# esp32.net
KiCad netlist of a schematic drawn in Altium Designer
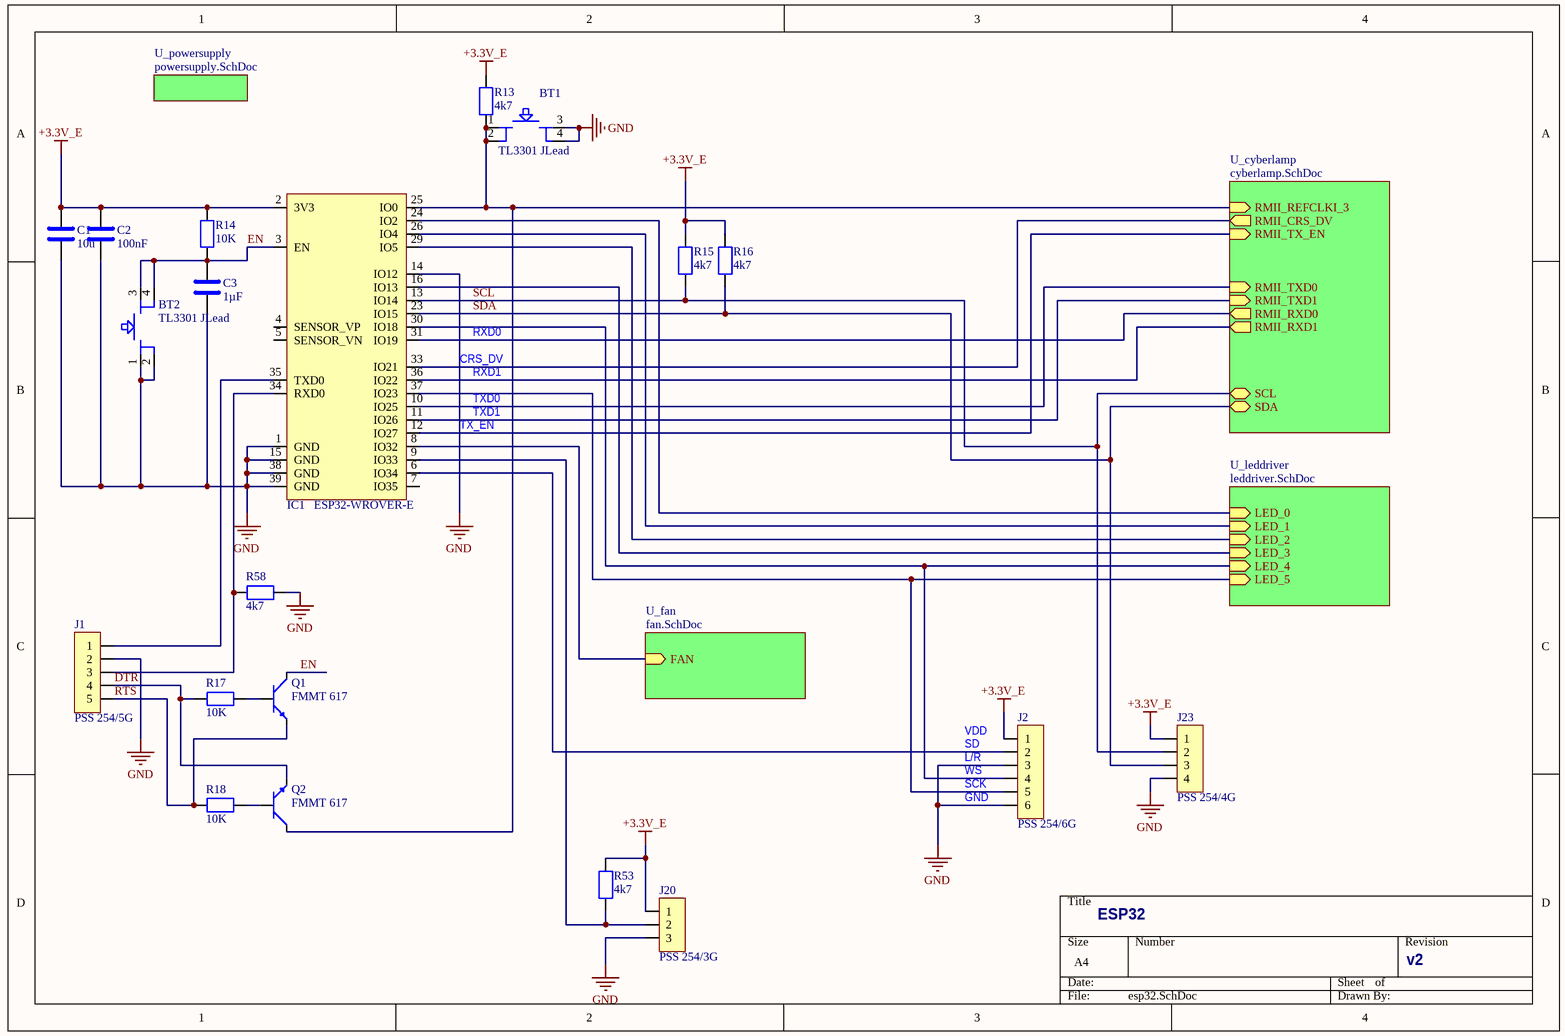
[diagram p0: esp32.SchDoc]

(export (version "E")
  (design (tool "Eeschema 10.0.6"))
  (components
    (comp (ref "BT1")
      (value "TL3301 JLead")
      (footprint "TL3301_Jlead")
      (description "TL3301 J-Lead button")
      (libsource (lib "switch_relais") (part "TK3301_jlead"))
    )
    (comp (ref "BT2")
      (value "TL3301 JLead")
      (footprint "TL3301_Jlead")
      (description "TL3301 J-Lead button")
      (libsource (lib "switch_relais") (part "TK3301_jlead"))
    )
    (comp (ref "C1")
      (value "10u")
      (footprint "1210")
      (description "10uF 63V X7R 1210")
      (fields (field (name "MOUSER PART") "81-GRM32ER71J106MA2L") (field (name "VOLTAGE") "63V"))
      (libsource (lib "capacitors") (part "10uF 63V X7R 1210"))
    )
    (comp (ref "C2")
      (value "100nF")
      (footprint "0603")
      (description "100nF 50V MLCC 0603")
      (fields (field (name "VOLTAGE") "50V"))
      (libsource (lib "capacitors") (part "100nF 50V MLCC 0603"))
    )
    (comp (ref "C3")
      (value "1µF")
      (footprint "0805")
      (description "1µF 25V MLCC 0805")
      (fields (field (name "VOLTAGE") "25V"))
      (libsource (lib "capacitor0805") (part "1µF 25V MLCC 0805"))
    )
    (comp (ref "IC1")
      (value "ESP32-WROVER-E")
      (footprint "ESP32-WROVER-I")
      (libsource (lib "microcontroller") (part "ESP32-WROVER-E-N16R2"))
    )
    (comp (ref "J1")
      (value "PSS 254/5G")
      (footprint "PSS 5pol")
      (description "PSS 5pol wire-to-board-connector")
      (libsource (lib "connectors_pss") (part "PSS 254/5G"))
    )
    (comp (ref "J2")
      (value "PSS 254/6G")
      (footprint "PSS 6pol")
      (description "PSS 6pol wire-to-board-connector")
      (libsource (lib "connectors_pss") (part "PSS 254/6G"))
    )
    (comp (ref "J20")
      (value "PSS 254/3G")
      (footprint "PSS 3pol")
      (description "PSS 3pol wire-to-board-connector")
      (libsource (lib "connectors_pss") (part "PSS 254/3G"))
    )
    (comp (ref "J23")
      (value "PSS 254/4G")
      (footprint "PSS 4pol")
      (description "PSS 4pol wire-to-board-connector")
      (libsource (lib "connectors_pss") (part "PSS 254/4G"))
    )
    (comp (ref "Q1")
      (value "FMMT 617")
      (footprint "SOT-23")
      (description "NPN switching Transistor, 3A")
      (libsource (lib "semiconductors") (part "FMMT 617"))
    )
    (comp (ref "Q2")
      (value "FMMT 617")
      (footprint "SOT-23")
      (description "NPN switching Transistor, 3A")
      (libsource (lib "semiconductors") (part "FMMT 617"))
    )
    (comp (ref "R13")
      (value "4k7")
      (footprint "res0603")
      (description "4k7 100mW 0603")
      (libsource (lib "resistors") (part "4k7 100mW 0603"))
    )
    (comp (ref "R14")
      (value "10K")
      (footprint "res0603")
      (description "10K 100mW 0603")
      (fields (field (name "TOLERANCE") "1%"))
      (libsource (lib "resistors") (part "10K 100mW 0603"))
    )
    (comp (ref "R15")
      (value "4k7")
      (footprint "res0603")
      (description "4k7 100mW 0603")
      (libsource (lib "resistors") (part "4k7 100mW 0603"))
    )
    (comp (ref "R16")
      (value "4k7")
      (footprint "res0603")
      (description "4k7 100mW 0603")
      (libsource (lib "resistors") (part "4k7 100mW 0603"))
    )
    (comp (ref "R17")
      (value "10K")
      (footprint "res0603")
      (description "10K 100mW 0603")
      (fields (field (name "TOLERANCE") "1%"))
      (libsource (lib "resistors") (part "10K 100mW 0603"))
    )
    (comp (ref "R18")
      (value "10K")
      (footprint "res0603")
      (description "10K 100mW 0603")
      (fields (field (name "TOLERANCE") "1%"))
      (libsource (lib "resistors") (part "10K 100mW 0603"))
    )
    (comp (ref "R53")
      (value "4k7")
      (footprint "res0603")
      (description "4k7 100mW 0603")
      (libsource (lib "resistors") (part "4k7 100mW 0603"))
    )
    (comp (ref "R58")
      (value "4k7")
      (footprint "res0603")
      (description "4k7 100mW 0603")
      (libsource (lib "resistors") (part "4k7 100mW 0603"))
    )
  )
  (nets
    (net (code "1") (name "+3.3V_E") (class "Default")
      (node (ref "C1") (pin "1") (pinfunction "1_1") (pintype "passive"))
      (node (ref "C2") (pin "1") (pinfunction "1_1") (pintype "passive"))
      (node (ref "IC1") (pin "2") (pinfunction "3V3_2") (pintype "passive"))
      (node (ref "J2") (pin "1") (pinfunction "1_1") (pintype "passive"))
      (node (ref "J20") (pin "1") (pinfunction "1_1") (pintype "passive"))
      (node (ref "J23") (pin "1") (pinfunction "1_1") (pintype "passive"))
      (node (ref "R13") (pin "2") (pinfunction "2_2") (pintype "passive"))
      (node (ref "R14") (pin "2") (pinfunction "2_2") (pintype "passive"))
      (node (ref "R15") (pin "2") (pinfunction "2_2") (pintype "passive"))
      (node (ref "R16") (pin "2") (pinfunction "2_2") (pintype "passive"))
      (node (ref "R53") (pin "2") (pinfunction "2_2") (pintype "passive"))
    )
    (net (code "2") (name "/DTR") (class "Default")
      (node (ref "J1") (pin "4") (pinfunction "4_4") (pintype "passive"))
      (node (ref "Q2") (pin "2") (pinfunction "2_2") (pintype "passive"))
      (node (ref "R17") (pin "2") (pinfunction "2_2") (pintype "passive"))
    )
    (net (code "3") (name "/EN") (class "Default")
      (node (ref "BT2") (pin "3") (pinfunction "3_3") (pintype "passive"))
      (node (ref "BT2") (pin "4") (pinfunction "4_4") (pintype "passive"))
      (node (ref "C3") (pin "1") (pinfunction "1_1") (pintype "passive"))
      (node (ref "IC1") (pin "3") (pinfunction "EN_3") (pintype "passive"))
      (node (ref "Q1") (pin "3") (pinfunction "3_3") (pintype "passive"))
      (node (ref "R14") (pin "1") (pinfunction "1_1") (pintype "passive"))
    )
    (net (code "4") (name "/FAN") (class "Default")
      (node (ref "IC1") (pin "8") (pinfunction "IO32_8") (pintype "passive"))
    )
    (net (code "5") (name "/LED_0") (class "Default")
      (node (ref "IC1") (pin "24") (pinfunction "IO2_24") (pintype "passive"))
    )
    (net (code "6") (name "/LED_1") (class "Default")
      (node (ref "IC1") (pin "26") (pinfunction "IO4_26") (pintype "passive"))
    )
    (net (code "7") (name "/LED_2") (class "Default")
      (node (ref "IC1") (pin "29") (pinfunction "IO5_29") (pintype "passive"))
    )
    (net (code "8") (name "/LED_3") (class "Default")
      (node (ref "IC1") (pin "16") (pinfunction "IO13_16") (pintype "passive"))
    )
    (net (code "9") (name "/LED_4") (class "Default")
      (node (ref "IC1") (pin "30") (pinfunction "IO18_30") (pintype "passive"))
      (node (ref "J2") (pin "4") (pinfunction "4_4") (pintype "passive"))
    )
    (net (code "10") (name "/LED_5") (class "Default")
      (node (ref "IC1") (pin "37") (pinfunction "IO23_37") (pintype "passive"))
      (node (ref "J2") (pin "5") (pinfunction "5_5") (pintype "passive"))
    )
    (net (code "11") (name "/RMII_CRS_DV") (class "Default")
      (node (ref "IC1") (pin "33") (pinfunction "IO21_33") (pintype "passive"))
    )
    (net (code "12") (name "/RMII_REFCLKI_3") (class "Default")
      (node (ref "BT1") (pin "1") (pinfunction "1_1") (pintype "passive"))
      (node (ref "BT1") (pin "2") (pinfunction "2_2") (pintype "passive"))
      (node (ref "IC1") (pin "25") (pinfunction "IO0_25") (pintype "passive"))
      (node (ref "Q2") (pin "3") (pinfunction "3_3") (pintype "passive"))
      (node (ref "R13") (pin "1") (pinfunction "1_1") (pintype "passive"))
    )
    (net (code "13") (name "/RMII_RXD0") (class "Default")
      (node (ref "IC1") (pin "31") (pinfunction "IO19_31") (pintype "passive"))
    )
    (net (code "14") (name "/RMII_RXD1") (class "Default")
      (node (ref "IC1") (pin "36") (pinfunction "IO22_36") (pintype "passive"))
    )
    (net (code "15") (name "/RMII_TXD0") (class "Default")
      (node (ref "IC1") (pin "10") (pinfunction "IO25_10") (pintype "passive"))
    )
    (net (code "16") (name "/RMII_TXD1") (class "Default")
      (node (ref "IC1") (pin "11") (pinfunction "IO26_11") (pintype "passive"))
    )
    (net (code "17") (name "/RMII_TX_EN") (class "Default")
      (node (ref "IC1") (pin "12") (pinfunction "IO27_12") (pintype "passive"))
    )
    (net (code "18") (name "/RTS") (class "Default")
      (node (ref "J1") (pin "5") (pinfunction "5_5") (pintype "passive"))
      (node (ref "Q1") (pin "2") (pinfunction "2_2") (pintype "passive"))
      (node (ref "R18") (pin "2") (pinfunction "2_2") (pintype "passive"))
    )
    (net (code "19") (name "/SCL") (class "Default")
      (node (ref "IC1") (pin "13") (pinfunction "IO14_13") (pintype "passive"))
      (node (ref "J23") (pin "2") (pinfunction "2_2") (pintype "passive"))
      (node (ref "R15") (pin "1") (pinfunction "1_1") (pintype "passive"))
    )
    (net (code "20") (name "/SDA") (class "Default")
      (node (ref "IC1") (pin "23") (pinfunction "IO15_23") (pintype "passive"))
      (node (ref "J23") (pin "3") (pinfunction "3_3") (pintype "passive"))
      (node (ref "R16") (pin "1") (pinfunction "1_1") (pintype "passive"))
    )
    (net (code "21") (name "GND") (class "Default")
      (node (ref "BT1") (pin "3") (pinfunction "3_3") (pintype "passive"))
      (node (ref "BT1") (pin "4") (pinfunction "4_4") (pintype "passive"))
      (node (ref "BT2") (pin "1") (pinfunction "1_1") (pintype "passive"))
      (node (ref "BT2") (pin "2") (pinfunction "2_2") (pintype "passive"))
      (node (ref "C1") (pin "2") (pinfunction "2_2") (pintype "passive"))
      (node (ref "C2") (pin "2") (pinfunction "2_2") (pintype "passive"))
      (node (ref "C3") (pin "2") (pinfunction "2_2") (pintype "passive"))
      (node (ref "IC1") (pin "1") (pinfunction "GND_1") (pintype "passive"))
      (node (ref "IC1") (pin "14") (pinfunction "IO12_14") (pintype "passive"))
      (node (ref "IC1") (pin "15") (pinfunction "GND_15") (pintype "passive"))
      (node (ref "IC1") (pin "38") (pinfunction "GND_38") (pintype "passive"))
      (node (ref "IC1") (pin "39") (pinfunction "GND_39") (pintype "passive"))
      (node (ref "J1") (pin "2") (pinfunction "2_2") (pintype "passive"))
      (node (ref "J2") (pin "3") (pinfunction "3_3") (pintype "passive"))
      (node (ref "J2") (pin "6") (pinfunction "6_6") (pintype "passive"))
      (node (ref "J20") (pin "3") (pinfunction "3_3") (pintype "passive"))
      (node (ref "J23") (pin "4") (pinfunction "4_4") (pintype "passive"))
      (node (ref "R58") (pin "1") (pinfunction "1_1") (pintype "passive"))
    )
    (net (code "22") (name "Net-(IC1-IO33)") (class "Default")
      (node (ref "IC1") (pin "9") (pinfunction "IO33_9") (pintype "passive"))
      (node (ref "J20") (pin "2") (pinfunction "2_2") (pintype "passive"))
      (node (ref "R53") (pin "1") (pinfunction "1_1") (pintype "passive"))
    )
    (net (code "23") (name "Net-(IC1-IO34)") (class "Default")
      (node (ref "IC1") (pin "6") (pinfunction "IO34_6") (pintype "passive"))
      (node (ref "J2") (pin "2") (pinfunction "2_2") (pintype "passive"))
    )
    (net (code "24") (name "Net-(IC1-RXD0)") (class "Default")
      (node (ref "IC1") (pin "34") (pinfunction "RXD0_34") (pintype "passive"))
      (node (ref "J1") (pin "3") (pinfunction "3_3") (pintype "passive"))
      (node (ref "R58") (pin "2") (pinfunction "2_2") (pintype "passive"))
    )
    (net (code "25") (name "Net-(IC1-TXD0)") (class "Default")
      (node (ref "IC1") (pin "35") (pinfunction "TXD0_35") (pintype "passive"))
      (node (ref "J1") (pin "1") (pinfunction "1_1") (pintype "passive"))
    )
    (net (code "26") (name "Net-(Q1-Pad1)") (class "Default")
      (node (ref "Q1") (pin "1") (pinfunction "1_1") (pintype "passive"))
      (node (ref "R17") (pin "1") (pinfunction "1_1") (pintype "passive"))
    )
    (net (code "27") (name "Net-(Q2-Pad1)") (class "Default")
      (node (ref "Q2") (pin "1") (pinfunction "1_1") (pintype "passive"))
      (node (ref "R18") (pin "1") (pinfunction "1_1") (pintype "passive"))
    )
    (net (code "28") (name "unconnected-(IC1-IO35-Pad7)") (class "Default")
      (node (ref "IC1") (pin "7") (pinfunction "IO35_7") (pintype "passive"))
    )
    (net (code "29") (name "unconnected-(IC1-SENSOR_VN-Pad5)") (class "Default")
      (node (ref "IC1") (pin "5") (pinfunction "SENSOR_VN_5") (pintype "passive"))
    )
    (net (code "30") (name "unconnected-(IC1-SENSOR_VP-Pad4)") (class "Default")
      (node (ref "IC1") (pin "4") (pinfunction "SENSOR_VP_4") (pintype "passive"))
    )
  )
)
